# design.net
KiCad netlist of a schematic drawn in Altium Designer
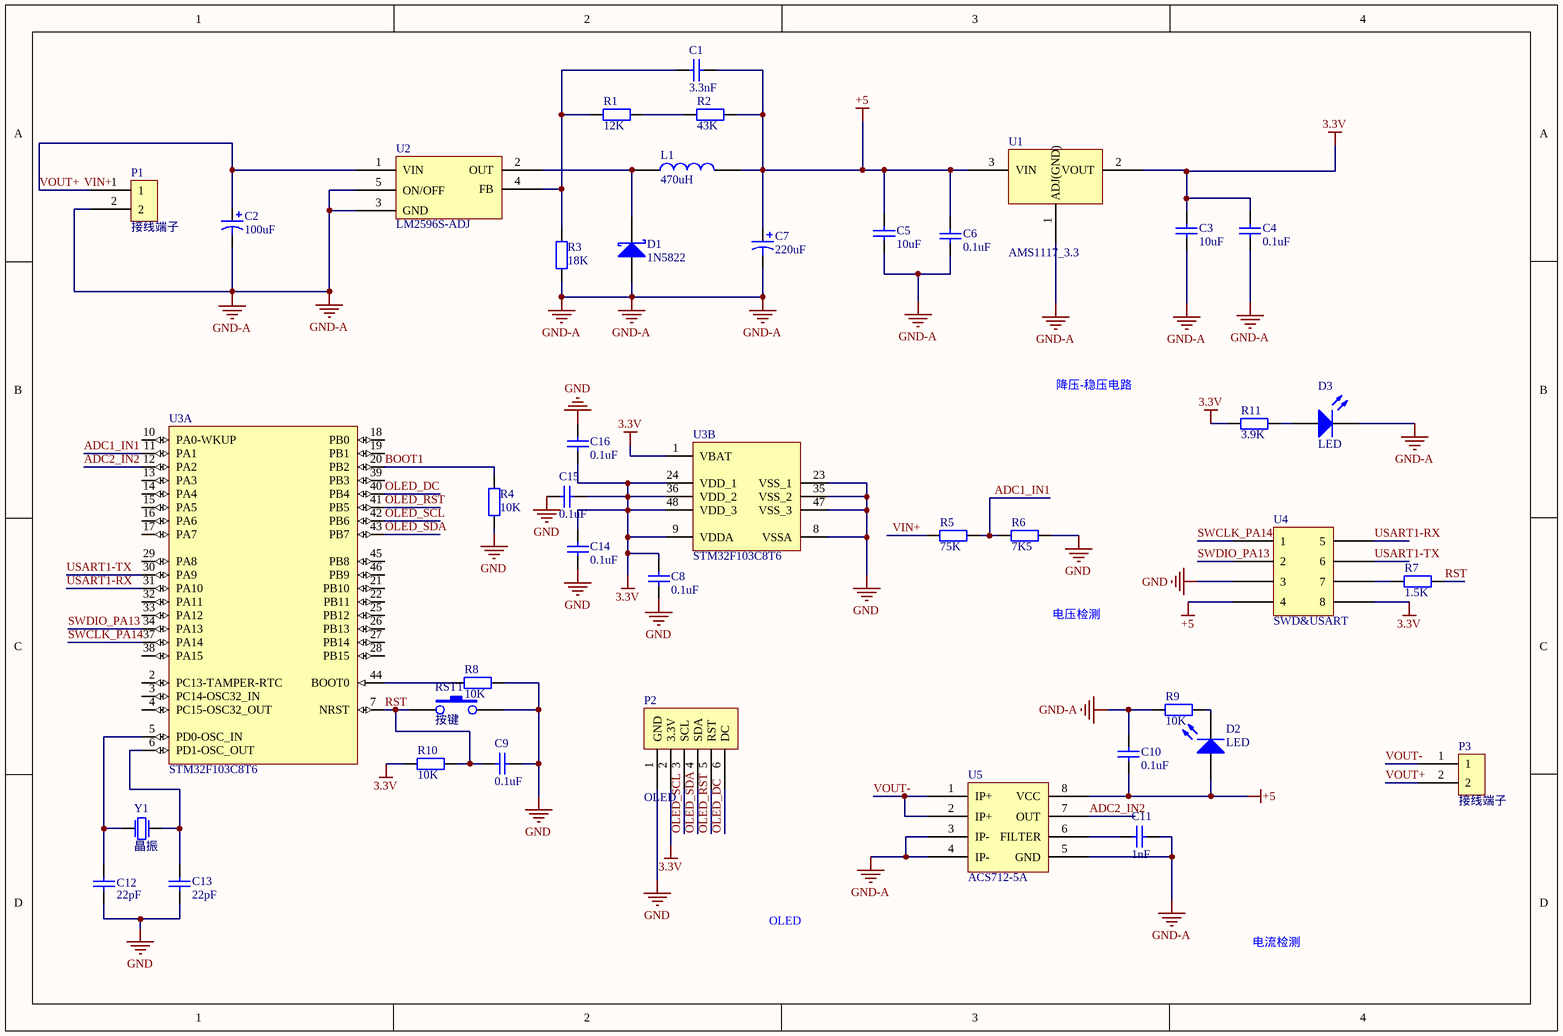
[diagram p0: 功率检测模块.SchDoc]

(export (version "E")
  (design (tool "Eeschema 10.0.6"))
  (components
    (comp (ref "C1")
      (value "3.3nF")
      (footprint "0805")
      (description "电容")
      (libsource (lib "功率检测模块") (part "电容"))
    )
    (comp (ref "C2") (value "100uF") (footprint "电解电容8*10.5") (libsource (lib "功率检测模块") (part "电解电容")))
    (comp (ref "C3")
      (value "10uF")
      (footprint "0805")
      (description "电容")
      (libsource (lib "功率检测模块") (part "电容"))
    )
    (comp (ref "C4")
      (value "0.1uF")
      (footprint "0805")
      (description "电容")
      (libsource (lib "功率检测模块") (part "电容"))
    )
    (comp (ref "C5")
      (value "10uF")
      (footprint "0805")
      (description "电容")
      (libsource (lib "功率检测模块") (part "电容"))
    )
    (comp (ref "C6")
      (value "0.1uF")
      (footprint "0805")
      (description "电容")
      (libsource (lib "功率检测模块") (part "电容"))
    )
    (comp (ref "C7") (value "220uF") (footprint "电解电容10*10.5") (libsource (lib "功率检测模块") (part "电解电容")))
    (comp (ref "C8")
      (value "0.1uF")
      (footprint "0805")
      (description "电容")
      (libsource (lib "功率检测模块") (part "电容"))
    )
    (comp (ref "C9")
      (value "0.1uF")
      (footprint "0805")
      (description "电容")
      (libsource (lib "功率检测模块") (part "电容"))
    )
    (comp (ref "C10")
      (value "0.1uF")
      (footprint "0805")
      (description "电容")
      (libsource (lib "功率检测模块") (part "电容"))
    )
    (comp (ref "C11")
      (value "1nF")
      (footprint "0805")
      (description "电容")
      (libsource (lib "功率检测模块") (part "电容"))
    )
    (comp (ref "C12")
      (value "22pF")
      (footprint "0805")
      (description "电容")
      (libsource (lib "功率检测模块") (part "电容"))
    )
    (comp (ref "C13")
      (value "22pF")
      (footprint "0805")
      (description "电容")
      (libsource (lib "功率检测模块") (part "电容"))
    )
    (comp (ref "C14")
      (value "0.1uF")
      (footprint "0805")
      (description "电容")
      (libsource (lib "功率检测模块") (part "电容"))
    )
    (comp (ref "C15")
      (value "0.1uF")
      (footprint "0805")
      (description "电容")
      (libsource (lib "功率检测模块") (part "电容"))
    )
    (comp (ref "C16")
      (value "0.1uF")
      (footprint "0805")
      (description "电容")
      (libsource (lib "功率检测模块") (part "电容"))
    )
    (comp (ref "D1")
      (value "1N5822")
      (footprint "SMA(DO-214AC)_S2")
      (libsource (lib "功率检测模块") (part "1N5822"))
    )
    (comp (ref "D2") (value "LED") (footprint "0805") (libsource (lib "功率检测模块") (part "LED")))
    (comp (ref "D3") (value "LED") (footprint "0805") (libsource (lib "功率检测模块") (part "LED")))
    (comp (ref "L1") (value "470uH") (footprint "电感") (libsource (lib "功率检测模块") (part "电感")))
    (comp (ref "P1")
      (value "接线端子")
      (footprint "接线端子")
      (description "螺旋式接线端子")
      (libsource (lib "功率检测模块") (part "接线端子"))
    )
    (comp (ref "P2") (value "OLED") (footprint "HDR6") (libsource (lib "功率检测模块") (part "OLED")))
    (comp (ref "P3")
      (value "接线端子")
      (footprint "接线端子")
      (description "螺旋式接线端子")
      (libsource (lib "功率检测模块") (part "接线端子"))
    )
    (comp (ref "R1")
      (value "12K")
      (footprint "0805")
      (description "贴片电阻")
      (libsource (lib "功率检测模块") (part "RES"))
    )
    (comp (ref "R2")
      (value "43K")
      (footprint "0805")
      (description "贴片电阻")
      (libsource (lib "功率检测模块") (part "RES"))
    )
    (comp (ref "R3")
      (value "18K")
      (footprint "0805")
      (description "贴片电阻")
      (libsource (lib "") (part "RES_2"))
    )
    (comp (ref "R4")
      (value "10K")
      (footprint "0805")
      (description "贴片电阻")
      (libsource (lib "") (part "RES_2"))
    )
    (comp (ref "R5")
      (value "75K")
      (footprint "0805")
      (description "贴片电阻")
      (libsource (lib "功率检测模块") (part "RES"))
    )
    (comp (ref "R6")
      (value "7K5")
      (footprint "0805")
      (description "贴片电阻")
      (libsource (lib "") (part "RES_1"))
    )
    (comp (ref "R7")
      (value "1.5K")
      (footprint "0805")
      (description "贴片电阻")
      (libsource (lib "功率检测模块") (part "RES"))
    )
    (comp (ref "R8")
      (value "10K")
      (footprint "0805")
      (description "贴片电阻")
      (libsource (lib "功率检测模块") (part "RES"))
    )
    (comp (ref "R9")
      (value "10K")
      (footprint "0805")
      (description "贴片电阻")
      (libsource (lib "") (part "RES_1"))
    )
    (comp (ref "R10")
      (value "10K")
      (footprint "0805")
      (description "贴片电阻")
      (libsource (lib "功率检测模块") (part "RES"))
    )
    (comp (ref "R11")
      (value "3.9K")
      (footprint "0805")
      (description "贴片电阻")
      (libsource (lib "功率检测模块") (part "RES"))
    )
    (comp (ref "RST1") (value "按键") (footprint "SWT3*4") (libsource (lib "功率检测模块") (part "按键")))
    (comp (ref "U1")
      (value "AMS1117_3.3")
      (footprint "SOT-223")
      (libsource (lib "功率检测模块") (part "AMS1117_3.3"))
    )
    (comp (ref "U2")
      (value "LM2596S-ADJ")
      (footprint "TO-263-5")
      (libsource (lib "功率检测模块") (part "LM2596S-ADJ"))
    )
    (comp (ref "U3")
      (value "STM32F103C8T6")
      (footprint "STM-LQFP48_L")
      (libsource (lib "功率检测模块") (part "STM32F103C8T6"))
    )
    (comp (ref "U4") (value "SWD&USART") (footprint "HDR2X4") (libsource (lib "功率检测模块") (part "SWD&USART")))
    (comp (ref "U5")
      (value "ACS712-5A")
      (footprint "SOP-8_208mil")
      (libsource (lib "功率检测模块") (part "ACS712-5A"))
    )
    (comp (ref "Y1") (value "晶振") (footprint "5032_2P") (libsource (lib "元件库") (part "晶振")))
  )
  (nets
    (net (code "1") (name "+5") (class "Default")
      (node (ref "C1") (pin "2") (pinfunction "2_2") (pintype "passive"))
      (node (ref "C10") (pin "1") (pinfunction "1_1") (pintype "passive"))
      (node (ref "C5") (pin "2") (pinfunction "2_2") (pintype "passive"))
      (node (ref "C6") (pin "2") (pinfunction "2_2") (pintype "passive"))
      (node (ref "C7") (pin "1") (pinfunction "1_1") (pintype "passive"))
      (node (ref "D2") (pin "1") (pinfunction "A_1") (pintype "passive"))
      (node (ref "L1") (pin "2") (pinfunction "2_2") (pintype "passive"))
      (node (ref "R2") (pin "2") (pinfunction "2_2") (pintype "passive"))
      (node (ref "U1") (pin "3") (pinfunction "VIN_3") (pintype "passive"))
      (node (ref "U4") (pin "4") (pinfunction "4_4") (pintype "passive"))
      (node (ref "U5") (pin "8") (pinfunction "VCC_8") (pintype "passive"))
    )
    (net (code "2") (name "/ADC1_IN1") (class "Default")
      (node (ref "R5") (pin "2") (pinfunction "2_2") (pintype "passive"))
      (node (ref "R6") (pin "2") (pinfunction "2_2") (pintype "passive"))
      (node (ref "U3") (pin "11") (pinfunction "PA1_11") (pintype "bidirectional"))
    )
    (net (code "3") (name "/ADC2_IN2") (class "Default")
      (node (ref "U3") (pin "12") (pinfunction "PA2_12") (pintype "bidirectional"))
      (node (ref "U5") (pin "7") (pinfunction "OUT_7") (pintype "passive"))
    )
    (net (code "4") (name "/BOOT1") (class "Default")
      (node (ref "R4") (pin "2") (pinfunction "2_2") (pintype "passive"))
      (node (ref "U3") (pin "20") (pinfunction "PB2_20") (pintype "bidirectional"))
    )
    (net (code "5") (name "/OLED_DC") (class "Default")
      (node (ref "P2") (pin "6") (pinfunction "DC_6") (pintype "passive"))
      (node (ref "U3") (pin "40") (pinfunction "PB4_40") (pintype "bidirectional"))
    )
    (net (code "6") (name "/OLED_RST") (class "Default")
      (node (ref "P2") (pin "5") (pinfunction "RST_5") (pintype "passive"))
      (node (ref "U3") (pin "41") (pinfunction "PB5_41") (pintype "bidirectional"))
    )
    (net (code "7") (name "/OLED_SCL") (class "Default")
      (node (ref "P2") (pin "3") (pinfunction "SCL_3") (pintype "passive"))
      (node (ref "U3") (pin "42") (pinfunction "PB6_42") (pintype "bidirectional"))
    )
    (net (code "8") (name "/OLED_SDA") (class "Default")
      (node (ref "P2") (pin "4") (pinfunction "SDA_4") (pintype "passive"))
      (node (ref "U3") (pin "43") (pinfunction "PB7_43") (pintype "bidirectional"))
    )
    (net (code "9") (name "/RST") (class "Default")
      (node (ref "C9") (pin "1") (pinfunction "1_1") (pintype "passive"))
      (node (ref "R10") (pin "2") (pinfunction "2_2") (pintype "passive"))
      (node (ref "R7") (pin "2") (pinfunction "2_2") (pintype "passive"))
      (node (ref "RST1") (pin "1") (pinfunction "1_1") (pintype "passive"))
      (node (ref "U3") (pin "7") (pinfunction "NRST_7") (pintype "bidirectional"))
    )
    (net (code "10") (name "/SWCLK_PA14") (class "Default")
      (node (ref "U3") (pin "37") (pinfunction "PA14_37") (pintype "bidirectional"))
      (node (ref "U4") (pin "1") (pinfunction "1_1") (pintype "passive"))
    )
    (net (code "11") (name "/SWDIO_PA13") (class "Default")
      (node (ref "U3") (pin "34") (pinfunction "PA13_34") (pintype "bidirectional"))
      (node (ref "U4") (pin "2") (pinfunction "2_2") (pintype "passive"))
    )
    (net (code "12") (name "/USART1-RX") (class "Default")
      (node (ref "U3") (pin "31") (pinfunction "PA10_31") (pintype "bidirectional"))
      (node (ref "U4") (pin "5") (pinfunction "5_5") (pintype "passive"))
    )
    (net (code "13") (name "/USART1-TX") (class "Default")
      (node (ref "U3") (pin "30") (pinfunction "PA9_30") (pintype "bidirectional"))
      (node (ref "U4") (pin "6") (pinfunction "6_6") (pintype "passive"))
    )
    (net (code "14") (name "/VIN+") (class "Default")
      (node (ref "C2") (pin "1") (pinfunction "1_1") (pintype "passive"))
      (node (ref "P1") (pin "1") (pinfunction "1_1") (pintype "passive"))
      (node (ref "P3") (pin "2") (pinfunction "2_2") (pintype "passive"))
      (node (ref "R5") (pin "1") (pinfunction "1_1") (pintype "passive"))
      (node (ref "U2") (pin "1") (pinfunction "VIN_1") (pintype "passive"))
    )
    (net (code "15") (name "/VOUT-") (class "Default")
      (node (ref "P3") (pin "1") (pinfunction "1_1") (pintype "passive"))
      (node (ref "U5") (pin "1") (pinfunction "IP+_1") (pintype "passive"))
      (node (ref "U5") (pin "2") (pinfunction "IP+_2") (pintype "passive"))
    )
    (net (code "16") (name "3.3V") (class "Default")
      (node (ref "C14") (pin "1") (pinfunction "1_1") (pintype "passive"))
      (node (ref "C15") (pin "2") (pinfunction "2_2") (pintype "passive"))
      (node (ref "C16") (pin "1") (pinfunction "1_1") (pintype "passive"))
      (node (ref "C3") (pin "2") (pinfunction "2_2") (pintype "passive"))
      (node (ref "C4") (pin "2") (pinfunction "2_2") (pintype "passive"))
      (node (ref "C8") (pin "2") (pinfunction "2_2") (pintype "passive"))
      (node (ref "P2") (pin "2") (pinfunction "3.3V_2") (pintype "passive"))
      (node (ref "R10") (pin "1") (pinfunction "1_1") (pintype "passive"))
      (node (ref "R11") (pin "1") (pinfunction "1_1") (pintype "passive"))
      (node (ref "U1") (pin "2") (pinfunction "VOUT_2") (pintype "passive"))
      (node (ref "U3") (pin "1") (pinfunction "VBAT_1") (pintype "power_in"))
      (node (ref "U3") (pin "24") (pinfunction "VDD_1_24") (pintype "power_in"))
      (node (ref "U3") (pin "36") (pinfunction "VDD_2_36") (pintype "power_in"))
      (node (ref "U3") (pin "48") (pinfunction "VDD_3_48") (pintype "power_in"))
      (node (ref "U3") (pin "9") (pinfunction "VDDA_9") (pintype "power_in"))
      (node (ref "U4") (pin "8") (pinfunction "8_8") (pintype "passive"))
    )
    (net (code "17") (name "GND") (class "Default")
      (node (ref "C12") (pin "1") (pinfunction "1_1") (pintype "passive"))
      (node (ref "C13") (pin "1") (pinfunction "1_1") (pintype "passive"))
      (node (ref "C14") (pin "2") (pinfunction "2_2") (pintype "passive"))
      (node (ref "C15") (pin "1") (pinfunction "1_1") (pintype "passive"))
      (node (ref "C16") (pin "2") (pinfunction "2_2") (pintype "passive"))
      (node (ref "C8") (pin "1") (pinfunction "1_1") (pintype "passive"))
      (node (ref "C9") (pin "2") (pinfunction "2_2") (pintype "passive"))
      (node (ref "P2") (pin "1") (pinfunction "GND_1") (pintype "passive"))
      (node (ref "R4") (pin "1") (pinfunction "1_1") (pintype "passive"))
      (node (ref "R6") (pin "1") (pinfunction "1_1") (pintype "passive"))
      (node (ref "R8") (pin "2") (pinfunction "2_2") (pintype "passive"))
      (node (ref "RST1") (pin "2") (pinfunction "2_2") (pintype "passive"))
      (node (ref "U3") (pin "23") (pinfunction "VSS_1_23") (pintype "power_in"))
      (node (ref "U3") (pin "35") (pinfunction "VSS_2_35") (pintype "power_in"))
      (node (ref "U3") (pin "47") (pinfunction "VSS_3_47") (pintype "power_in"))
      (node (ref "U3") (pin "8") (pinfunction "VSSA_8") (pintype "power_in"))
      (node (ref "U4") (pin "3") (pinfunction "3_3") (pintype "passive"))
    )
    (net (code "18") (name "GND-A") (class "Default")
      (node (ref "C10") (pin "2") (pinfunction "2_2") (pintype "passive"))
      (node (ref "C11") (pin "2") (pinfunction "2_2") (pintype "passive"))
      (node (ref "C2") (pin "2") (pinfunction "2_2") (pintype "passive"))
      (node (ref "C3") (pin "1") (pinfunction "1_1") (pintype "passive"))
      (node (ref "C4") (pin "1") (pinfunction "1_1") (pintype "passive"))
      (node (ref "C5") (pin "1") (pinfunction "1_1") (pintype "passive"))
      (node (ref "C6") (pin "1") (pinfunction "1_1") (pintype "passive"))
      (node (ref "C7") (pin "2") (pinfunction "2_2") (pintype "passive"))
      (node (ref "D1") (pin "1") (pinfunction "A_1") (pintype "passive"))
      (node (ref "D3") (pin "2") (pinfunction "K_2") (pintype "passive"))
      (node (ref "P1") (pin "2") (pinfunction "2_2") (pintype "passive"))
      (node (ref "R3") (pin "1") (pinfunction "1_1") (pintype "passive"))
      (node (ref "R9") (pin "2") (pinfunction "2_2") (pintype "passive"))
      (node (ref "U1") (pin "1") (pinfunction "ADJ(GND)_1") (pintype "passive"))
      (node (ref "U2") (pin "3") (pinfunction "GND_3") (pintype "passive"))
      (node (ref "U2") (pin "5") (pinfunction "ON/OFF_5") (pintype "passive"))
      (node (ref "U5") (pin "3") (pinfunction "IP-_3") (pintype "passive"))
      (node (ref "U5") (pin "4") (pinfunction "IP-_4") (pintype "passive"))
      (node (ref "U5") (pin "5") (pinfunction "GND_5") (pintype "passive"))
    )
    (net (code "19") (name "Net-(D1-K)") (class "Default")
      (node (ref "D1") (pin "2") (pinfunction "K_2") (pintype "passive"))
      (node (ref "L1") (pin "1") (pinfunction "1_1") (pintype "passive"))
      (node (ref "U2") (pin "2") (pinfunction "OUT_2") (pintype "passive"))
    )
    (net (code "20") (name "Net-(D2-K)") (class "Default")
      (node (ref "D2") (pin "2") (pinfunction "K_2") (pintype "passive"))
      (node (ref "R9") (pin "1") (pinfunction "1_1") (pintype "passive"))
    )
    (net (code "21") (name "Net-(D3-A)") (class "Default")
      (node (ref "D3") (pin "1") (pinfunction "A_1") (pintype "passive"))
      (node (ref "R11") (pin "2") (pinfunction "2_2") (pintype "passive"))
    )
    (net (code "22") (name "Net-(R1-Pad2)") (class "Default")
      (node (ref "R1") (pin "2") (pinfunction "2_2") (pintype "passive"))
      (node (ref "R2") (pin "1") (pinfunction "1_1") (pintype "passive"))
    )
    (net (code "23") (name "Net-(R7-Pad1)") (class "Default")
      (node (ref "R7") (pin "1") (pinfunction "1_1") (pintype "passive"))
      (node (ref "U4") (pin "7") (pinfunction "7_7") (pintype "passive"))
    )
    (net (code "24") (name "Net-(U2-FB)") (class "Default")
      (node (ref "C1") (pin "1") (pinfunction "1_1") (pintype "passive"))
      (node (ref "R1") (pin "1") (pinfunction "1_1") (pintype "passive"))
      (node (ref "R3") (pin "2") (pinfunction "2_2") (pintype "passive"))
      (node (ref "U2") (pin "4") (pinfunction "FB_4") (pintype "passive"))
    )
    (net (code "25") (name "Net-(U3A-BOOT0)") (class "Default")
      (node (ref "R8") (pin "1") (pinfunction "1_1") (pintype "passive"))
      (node (ref "U3") (pin "44") (pinfunction "BOOT0_44") (pintype "input"))
    )
    (net (code "26") (name "Net-(U3A-PD0-OSC_IN)") (class "Default")
      (node (ref "C12") (pin "2") (pinfunction "2_2") (pintype "passive"))
      (node (ref "U3") (pin "5") (pinfunction "PD0-OSC_IN_5") (pintype "bidirectional"))
      (node (ref "Y1") (pin "1") (pinfunction "P1_1") (pintype "passive"))
    )
    (net (code "27") (name "Net-(U3A-PD1-OSC_OUT)") (class "Default")
      (node (ref "C13") (pin "2") (pinfunction "2_2") (pintype "passive"))
      (node (ref "U3") (pin "6") (pinfunction "PD1-OSC_OUT_6") (pintype "bidirectional"))
      (node (ref "Y1") (pin "2") (pinfunction "P2_2") (pintype "passive"))
    )
    (net (code "28") (name "Net-(U5-FILTER)") (class "Default")
      (node (ref "C11") (pin "1") (pinfunction "1_1") (pintype "passive"))
      (node (ref "U5") (pin "6") (pinfunction "FILTER_6") (pintype "passive"))
    )
    (net (code "29") (name "unconnected-(U3A-PA0-WKUP-Pad10)") (class "Default")
      (node (ref "U3") (pin "10") (pinfunction "PA0-WKUP_10") (pintype "bidirectional"))
    )
    (net (code "30") (name "unconnected-(U3A-PA3-Pad13)") (class "Default")
      (node (ref "U3") (pin "13") (pinfunction "PA3_13") (pintype "bidirectional"))
    )
    (net (code "31") (name "unconnected-(U3A-PA4-Pad14)") (class "Default")
      (node (ref "U3") (pin "14") (pinfunction "PA4_14") (pintype "bidirectional"))
    )
    (net (code "32") (name "unconnected-(U3A-PA5-Pad15)") (class "Default")
      (node (ref "U3") (pin "15") (pinfunction "PA5_15") (pintype "bidirectional"))
    )
    (net (code "33") (name "unconnected-(U3A-PA6-Pad16)") (class "Default")
      (node (ref "U3") (pin "16") (pinfunction "PA6_16") (pintype "bidirectional"))
    )
    (net (code "34") (name "unconnected-(U3A-PA7-Pad17)") (class "Default")
      (node (ref "U3") (pin "17") (pinfunction "PA7_17") (pintype "bidirectional"))
    )
    (net (code "35") (name "unconnected-(U3A-PA8-Pad29)") (class "Default")
      (node (ref "U3") (pin "29") (pinfunction "PA8_29") (pintype "bidirectional"))
    )
    (net (code "36") (name "unconnected-(U3A-PA11-Pad32)") (class "Default")
      (node (ref "U3") (pin "32") (pinfunction "PA11_32") (pintype "bidirectional"))
    )
    (net (code "37") (name "unconnected-(U3A-PA12-Pad33)") (class "Default")
      (node (ref "U3") (pin "33") (pinfunction "PA12_33") (pintype "bidirectional"))
    )
    (net (code "38") (name "unconnected-(U3A-PA15-Pad38)") (class "Default")
      (node (ref "U3") (pin "38") (pinfunction "PA15_38") (pintype "bidirectional"))
    )
    (net (code "39") (name "unconnected-(U3A-PB0-Pad18)") (class "Default")
      (node (ref "U3") (pin "18") (pinfunction "PB0_18") (pintype "bidirectional"))
    )
    (net (code "40") (name "unconnected-(U3A-PB1-Pad19)") (class "Default")
      (node (ref "U3") (pin "19") (pinfunction "PB1_19") (pintype "bidirectional"))
    )
    (net (code "41") (name "unconnected-(U3A-PB3-Pad39)") (class "Default")
      (node (ref "U3") (pin "39") (pinfunction "PB3_39") (pintype "bidirectional"))
    )
    (net (code "42") (name "unconnected-(U3A-PB8-Pad45)") (class "Default")
      (node (ref "U3") (pin "45") (pinfunction "PB8_45") (pintype "bidirectional"))
    )
    (net (code "43") (name "unconnected-(U3A-PB9-Pad46)") (class "Default")
      (node (ref "U3") (pin "46") (pinfunction "PB9_46") (pintype "bidirectional"))
    )
    (net (code "44") (name "unconnected-(U3A-PB10-Pad21)") (class "Default")
      (node (ref "U3") (pin "21") (pinfunction "PB10_21") (pintype "bidirectional"))
    )
    (net (code "45") (name "unconnected-(U3A-PB11-Pad22)") (class "Default")
      (node (ref "U3") (pin "22") (pinfunction "PB11_22") (pintype "bidirectional"))
    )
    (net (code "46") (name "unconnected-(U3A-PB12-Pad25)") (class "Default")
      (node (ref "U3") (pin "25") (pinfunction "PB12_25") (pintype "bidirectional"))
    )
    (net (code "47") (name "unconnected-(U3A-PB13-Pad26)") (class "Default")
      (node (ref "U3") (pin "26") (pinfunction "PB13_26") (pintype "bidirectional"))
    )
    (net (code "48") (name "unconnected-(U3A-PB14-Pad27)") (class "Default")
      (node (ref "U3") (pin "27") (pinfunction "PB14_27") (pintype "bidirectional"))
    )
    (net (code "49") (name "unconnected-(U3A-PB15-Pad28)") (class "Default")
      (node (ref "U3") (pin "28") (pinfunction "PB15_28") (pintype "bidirectional"))
    )
    (net (code "50") (name "unconnected-(U3A-PC13-TAMPER-RTC-Pad2)") (class "Default")
      (node (ref "U3") (pin "2") (pinfunction "PC13-TAMPER-RTC_2") (pintype "bidirectional"))
    )
    (net (code "51") (name "unconnected-(U3A-PC14-OSC32_IN-Pad3)") (class "Default")
      (node (ref "U3") (pin "3") (pinfunction "PC14-OSC32_IN_3") (pintype "bidirectional"))
    )
    (net (code "52") (name "unconnected-(U3A-PC15-OSC32_OUT-Pad4)") (class "Default")
      (node (ref "U3") (pin "4") (pinfunction "PC15-OSC32_OUT_4") (pintype "bidirectional"))
    )
  )
)
